# POT_10x8.net
KiCad netlist of a schematic drawn in Altium Designer
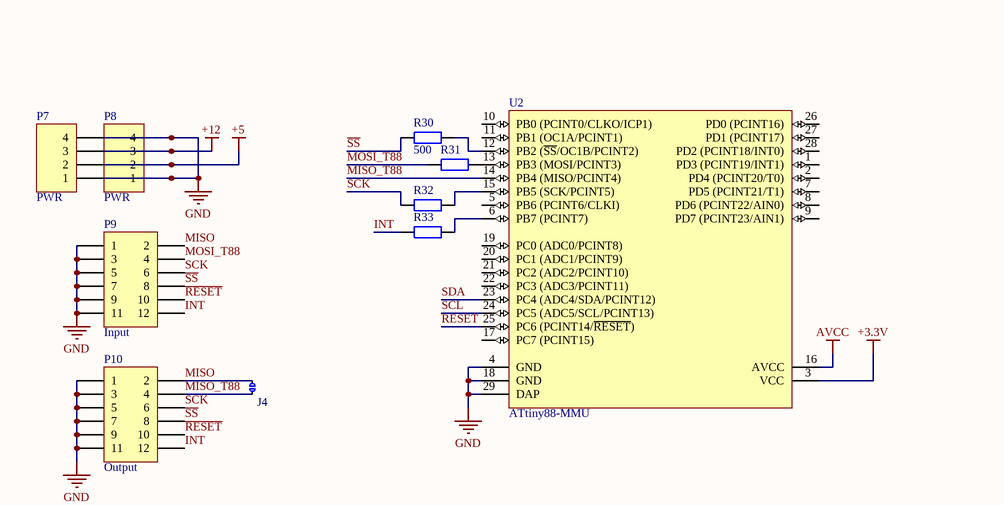
[diagram p0: POT 10x8.SchDoc, top left]
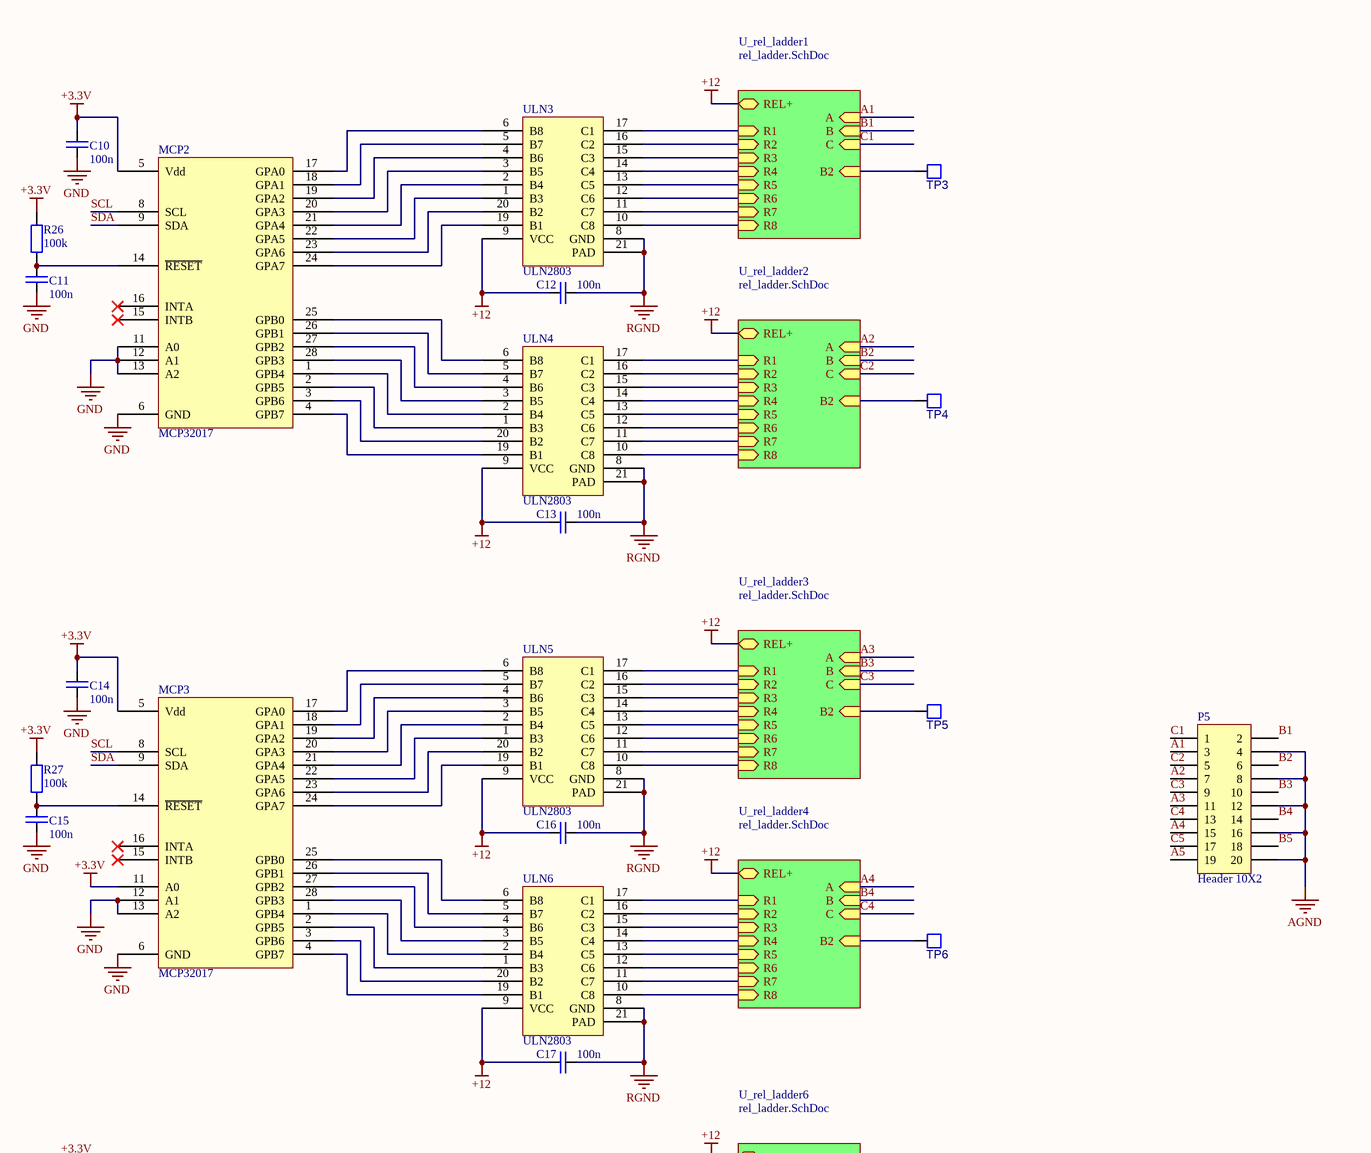
[diagram p1: POT 10x8.SchDoc, top right]
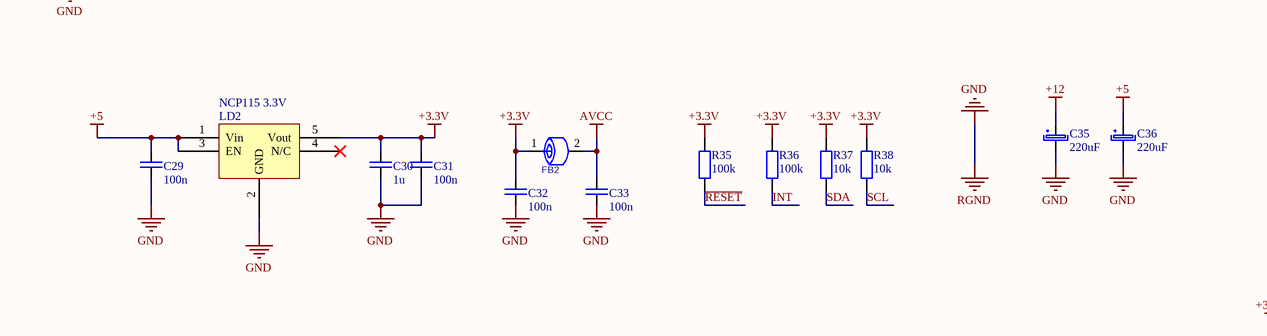
[diagram p2: POT 10x8.SchDoc, bottom left]
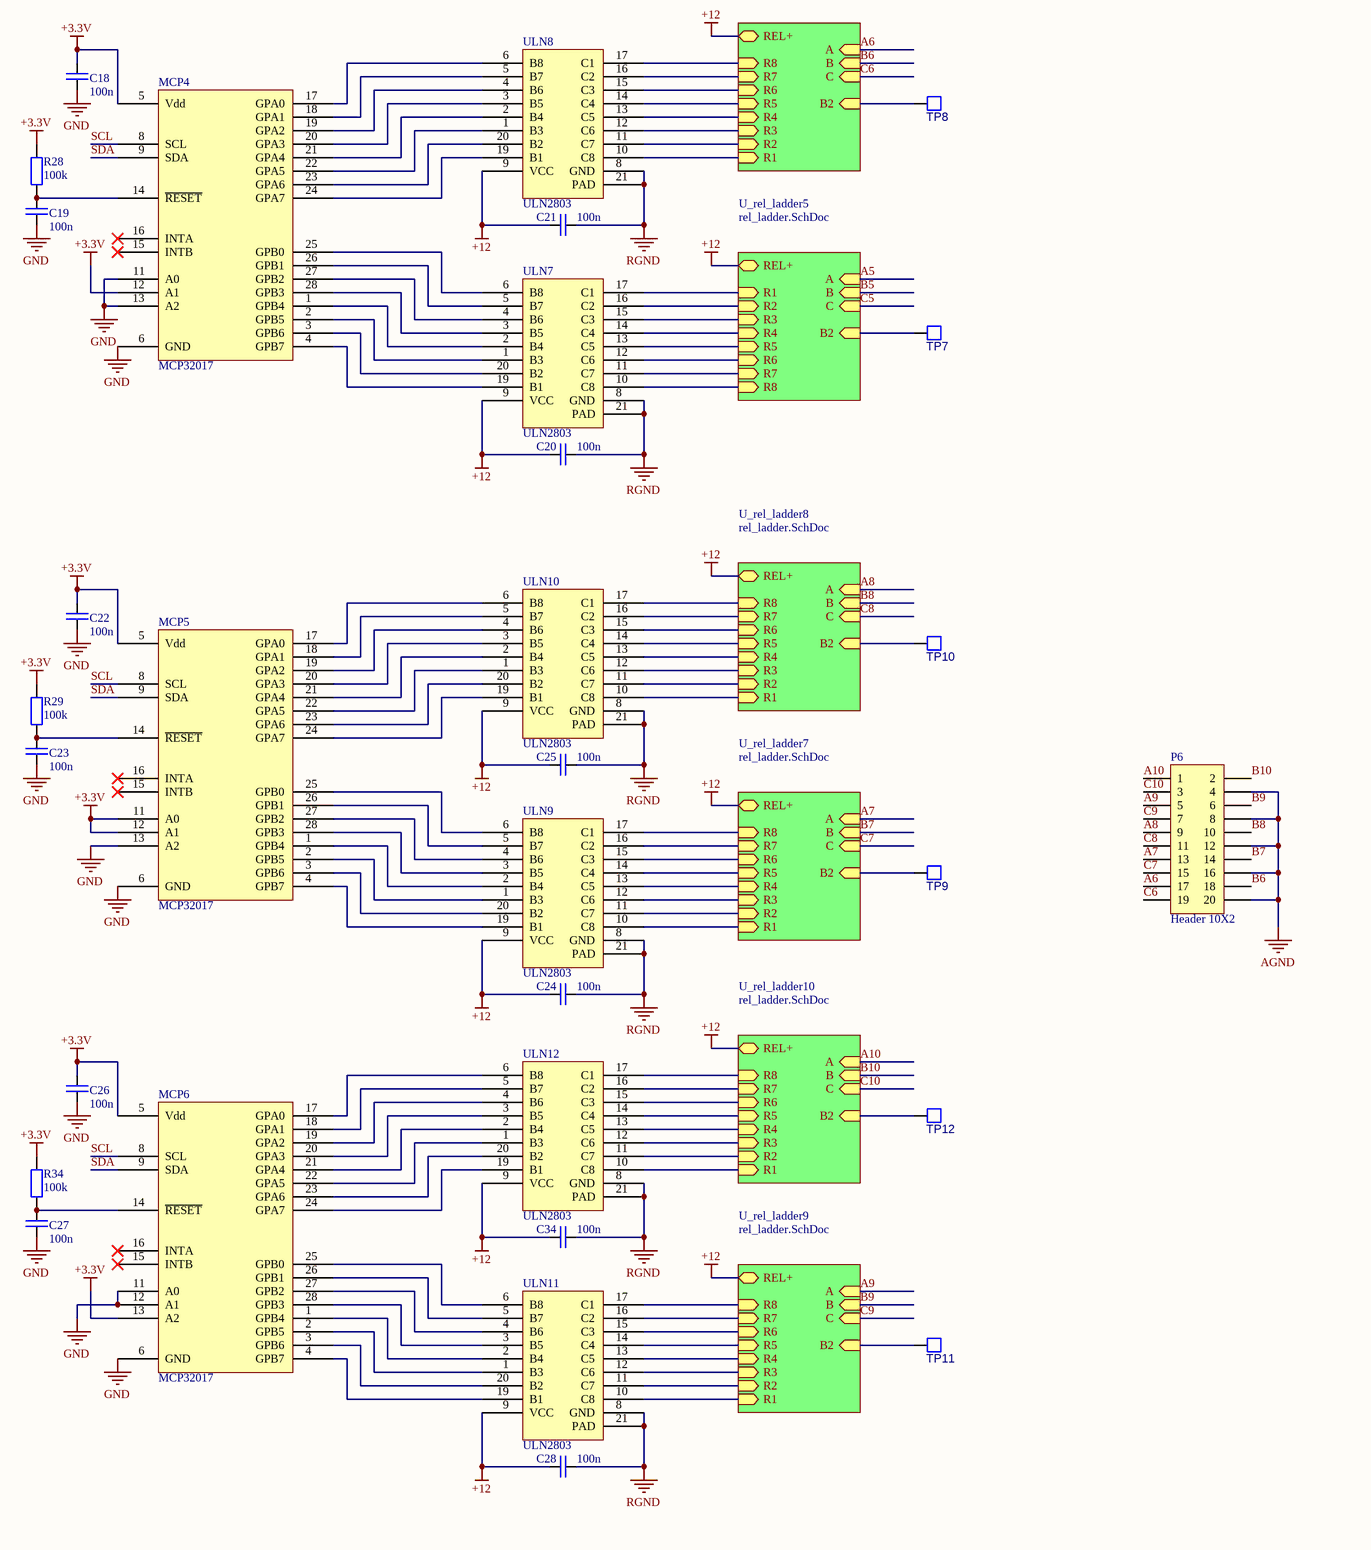
[diagram p3: POT 10x8.SchDoc, bottom right]

(export (version "E")
  (design (tool "Eeschema 10.0.6"))
  (components
    (comp (ref "C10")
      (value "100n")
      (footprint "R1005_0402i_L")
      (description "Capacitor")
      (libsource (lib "General") (part "C"))
    )
    (comp (ref "C11")
      (value "100n")
      (footprint "R1005_0402i_L")
      (description "Capacitor")
      (libsource (lib "General") (part "C"))
    )
    (comp (ref "C12")
      (value "100n")
      (footprint "R1005_0402i_L")
      (description "Capacitor")
      (libsource (lib "General") (part "C"))
    )
    (comp (ref "C13")
      (value "100n")
      (footprint "R1005_0402i_L")
      (description "Capacitor")
      (libsource (lib "General") (part "C"))
    )
    (comp (ref "C14")
      (value "100n")
      (footprint "R1005_0402i_L")
      (description "Capacitor")
      (libsource (lib "General") (part "C"))
    )
    (comp (ref "C15")
      (value "100n")
      (footprint "R1005_0402i_L")
      (description "Capacitor")
      (libsource (lib "General") (part "C"))
    )
    (comp (ref "C16")
      (value "100n")
      (footprint "R1005_0402i_L")
      (description "Capacitor")
      (libsource (lib "General") (part "C"))
    )
    (comp (ref "C17")
      (value "100n")
      (footprint "R1005_0402i_L")
      (description "Capacitor")
      (libsource (lib "General") (part "C"))
    )
    (comp (ref "C18")
      (value "100n")
      (footprint "R1005_0402i_L")
      (description "Capacitor")
      (libsource (lib "General") (part "C"))
    )
    (comp (ref "C19")
      (value "100n")
      (footprint "R1005_0402i_L")
      (description "Capacitor")
      (libsource (lib "General") (part "C"))
    )
    (comp (ref "C20")
      (value "100n")
      (footprint "R1005_0402i_L")
      (description "Capacitor")
      (libsource (lib "General") (part "C"))
    )
    (comp (ref "C21")
      (value "100n")
      (footprint "R1005_0402i_L")
      (description "Capacitor")
      (libsource (lib "General") (part "C"))
    )
    (comp (ref "C22")
      (value "100n")
      (footprint "R1005_0402i_L")
      (description "Capacitor")
      (libsource (lib "General") (part "C"))
    )
    (comp (ref "C23")
      (value "100n")
      (footprint "R1005_0402i_L")
      (description "Capacitor")
      (libsource (lib "General") (part "C"))
    )
    (comp (ref "C24")
      (value "100n")
      (footprint "R1005_0402i_L")
      (description "Capacitor")
      (libsource (lib "General") (part "C"))
    )
    (comp (ref "C25")
      (value "100n")
      (footprint "R1005_0402i_L")
      (description "Capacitor")
      (libsource (lib "General") (part "C"))
    )
    (comp (ref "C26")
      (value "100n")
      (footprint "R1005_0402i_L")
      (description "Capacitor")
      (libsource (lib "General") (part "C"))
    )
    (comp (ref "C27")
      (value "100n")
      (footprint "R1005_0402i_L")
      (description "Capacitor")
      (libsource (lib "General") (part "C"))
    )
    (comp (ref "C28")
      (value "100n")
      (footprint "R1005_0402i_L")
      (description "Capacitor")
      (libsource (lib "General") (part "C"))
    )
    (comp (ref "C29")
      (value "100n")
      (footprint "R1005_0402i_L")
      (description "Capacitor")
      (libsource (lib "General") (part "C"))
    )
    (comp (ref "C30")
      (value "1u")
      (footprint "C1608_0603I_L")
      (description "Capacitor")
      (libsource (lib "General") (part "C"))
    )
    (comp (ref "C31")
      (value "100n")
      (footprint "R1005_0402i_L")
      (description "Capacitor")
      (libsource (lib "General") (part "C"))
    )
    (comp (ref "C32")
      (value "100n")
      (footprint "R1005_0402i_L")
      (description "Capacitor")
      (libsource (lib "General") (part "C"))
    )
    (comp (ref "C33")
      (value "100n")
      (footprint "R1005_0402i_L")
      (description "Capacitor")
      (libsource (lib "General") (part "C"))
    )
    (comp (ref "C34")
      (value "100n")
      (footprint "R1005_0402i_L")
      (description "Capacitor")
      (libsource (lib "General") (part "C"))
    )
    (comp (ref "C35")
      (value "220uF")
      (footprint "C AlElko 5x11 R2")
      (description "Capacitor Polarized")
      (libsource (lib "General") (part "C+"))
    )
    (comp (ref "C36")
      (value "220uF")
      (footprint "C AlElko 5x11 R2")
      (description "Capacitor Polarized")
      (libsource (lib "General") (part "C+"))
    )
    (comp (ref "FB2")
      (value "FERITTE BEAD")
      (footprint "R1608_0603I_L")
      (libsource (lib "General") (part "FERITTE BEAD"))
    )
    (comp (ref "J4")
      (value "Terminator")
      (footprint "solderJumper")
      (libsource (lib "Kon_Tipk") (part "JMP_mini"))
    )
    (comp (ref "LD2")
      (value "NCP115 3.3V")
      (footprint "TSOP95P280X110-6L")
      (libsource (lib "led_ring") (part "NCP115 3.3V"))
    )
    (comp (ref "MCP2")
      (value "MCP32017")
      (footprint "MCP23017 QFN")
      (libsource (lib "Schlib1") (part "MCP32017"))
    )
    (comp (ref "MCP3")
      (value "MCP32017")
      (footprint "MCP23017 QFN")
      (libsource (lib "Schlib1") (part "MCP32017"))
    )
    (comp (ref "MCP4")
      (value "MCP32017")
      (footprint "MCP23017 QFN")
      (libsource (lib "Schlib1") (part "MCP32017"))
    )
    (comp (ref "MCP5")
      (value "MCP32017")
      (footprint "MCP23017 QFN")
      (libsource (lib "Schlib1") (part "MCP32017"))
    )
    (comp (ref "MCP6")
      (value "MCP32017")
      (footprint "MCP23017 QFN")
      (libsource (lib "Schlib1") (part "MCP32017"))
    )
    (comp (ref "P5")
      (value "Header 10X2")
      (footprint "HDR2X10")
      (description "Header, 10-Pin, Dual row")
      (fields (field (name "PUBLISHER") "Altium Limited"))
      (libsource (lib "Miscellaneous Connectors") (part "Header 10X2"))
    )
    (comp (ref "P6")
      (value "Header 10X2")
      (footprint "HDR2X10")
      (description "Header, 10-Pin, Dual row")
      (fields (field (name "PUBLISHER") "Altium Limited"))
      (libsource (lib "Miscellaneous Connectors") (part "Header 10X2"))
    )
    (comp (ref "P7")
      (value "PWR")
      (footprint "HDR1X4")
      (description "Header, 4-Pin")
      (fields (field (name "PUBLISHER") "Altium Limited"))
      (libsource (lib "Miscellaneous Connectors") (part "Header 4"))
    )
    (comp (ref "P8")
      (value "PWR")
      (footprint "HDR1X4")
      (description "Header, 4-Pin")
      (fields (field (name "PUBLISHER") "Altium Limited"))
      (libsource (lib "Miscellaneous Connectors") (part "Header 4"))
    )
    (comp (ref "P9")
      (value "Input")
      (footprint "1.27mm SMD conn")
      (description "Header, 6-Pin, Dual row")
      (fields (field (name "PUBLISHER") "Altium Limited"))
      (libsource (lib "Miscellaneous Connectors") (part "Header 6X2"))
    )
    (comp (ref "P10")
      (value "Output")
      (footprint "1.27mm SMD conn")
      (description "Header, 6-Pin, Dual row")
      (fields (field (name "PUBLISHER") "Altium Limited"))
      (libsource (lib "Miscellaneous Connectors") (part "Header 6X2"))
    )
    (comp (ref "R26")
      (value "100k")
      (footprint "R1005_0402i_L")
      (description "R")
      (libsource (lib "General") (part "R"))
    )
    (comp (ref "R27")
      (value "100k")
      (footprint "R1005_0402i_L")
      (description "R")
      (libsource (lib "General") (part "R"))
    )
    (comp (ref "R28")
      (value "100k")
      (footprint "R1005_0402i_L")
      (description "R")
      (libsource (lib "General") (part "R"))
    )
    (comp (ref "R29")
      (value "100k")
      (footprint "R1005_0402i_L")
      (description "R")
      (libsource (lib "General") (part "R"))
    )
    (comp (ref "R30")
      (value "500")
      (footprint "R1005_0402i_L")
      (description "R")
      (libsource (lib "General") (part "R"))
    )
    (comp (ref "R31")
      (value "500")
      (footprint "R1005_0402i_L")
      (description "R")
      (libsource (lib "General") (part "R"))
    )
    (comp (ref "R32")
      (value "500")
      (footprint "R1005_0402i_L")
      (description "R")
      (libsource (lib "General") (part "R"))
    )
    (comp (ref "R33")
      (value "500")
      (footprint "R1005_0402i_L")
      (description "R")
      (libsource (lib "General") (part "R"))
    )
    (comp (ref "R34")
      (value "100k")
      (footprint "R1005_0402i_L")
      (description "R")
      (libsource (lib "General") (part "R"))
    )
    (comp (ref "R35")
      (value "100k")
      (footprint "R1005_0402i_L")
      (description "R")
      (libsource (lib "General") (part "R"))
    )
    (comp (ref "R36")
      (value "100k")
      (footprint "R1005_0402i_L")
      (description "R")
      (libsource (lib "General") (part "R"))
    )
    (comp (ref "R37")
      (value "10k")
      (footprint "R1005_0402i_L")
      (description "R")
      (libsource (lib "General") (part "R"))
    )
    (comp (ref "R38")
      (value "10k")
      (footprint "R1005_0402i_L")
      (description "R")
      (libsource (lib "General") (part "R"))
    )
    (comp (ref "TP3") (value "PAD") (footprint "PAD_CIRC_HOLE") (libsource (lib "General") (part "PAD")))
    (comp (ref "TP4") (value "PAD") (footprint "PAD_CIRC_HOLE") (libsource (lib "General") (part "PAD")))
    (comp (ref "TP5") (value "PAD") (footprint "PAD_CIRC_HOLE") (libsource (lib "General") (part "PAD")))
    (comp (ref "TP6") (value "PAD") (footprint "PAD_CIRC_HOLE") (libsource (lib "General") (part "PAD")))
    (comp (ref "TP7") (value "PAD") (footprint "PAD_CIRC_HOLE") (libsource (lib "General") (part "PAD")))
    (comp (ref "TP8") (value "PAD") (footprint "PAD_CIRC_HOLE") (libsource (lib "General") (part "PAD")))
    (comp (ref "TP9") (value "PAD") (footprint "PAD_CIRC_HOLE") (libsource (lib "General") (part "PAD")))
    (comp (ref "TP10") (value "PAD") (footprint "PAD_CIRC_HOLE") (libsource (lib "General") (part "PAD")))
    (comp (ref "TP11") (value "PAD") (footprint "PAD_CIRC_HOLE") (libsource (lib "General") (part "PAD")))
    (comp (ref "TP12") (value "PAD") (footprint "PAD_CIRC_HOLE") (libsource (lib "General") (part "PAD")))
    (comp (ref "U2")
      (value "ATtiny88-MMU")
      (footprint "28M1_N")
      (fields (field (name "PUBLISHER") "Altium Limited"))
      (libsource (lib "Encoder_w_LED_ring") (part "ATtiny88-MMU"))
    )
    (comp (ref "ULN3")
      (value "ULN2803")
      (footprint "QFN127P600-8N")
      (libsource (lib "Schlib1") (part "ULN2803"))
    )
    (comp (ref "ULN4")
      (value "ULN2803")
      (footprint "QFN127P600-8N")
      (libsource (lib "Schlib1") (part "ULN2803"))
    )
    (comp (ref "ULN5")
      (value "ULN2803")
      (footprint "QFN127P600-8N")
      (libsource (lib "Schlib1") (part "ULN2803"))
    )
    (comp (ref "ULN6")
      (value "ULN2803")
      (footprint "QFN127P600-8N")
      (libsource (lib "Schlib1") (part "ULN2803"))
    )
    (comp (ref "ULN7")
      (value "ULN2803")
      (footprint "QFN127P600-8N")
      (libsource (lib "Schlib1") (part "ULN2803"))
    )
    (comp (ref "ULN8")
      (value "ULN2803")
      (footprint "QFN127P600-8N")
      (libsource (lib "Schlib1") (part "ULN2803"))
    )
    (comp (ref "ULN9")
      (value "ULN2803")
      (footprint "QFN127P600-8N")
      (libsource (lib "Schlib1") (part "ULN2803"))
    )
    (comp (ref "ULN10")
      (value "ULN2803")
      (footprint "QFN127P600-8N")
      (libsource (lib "Schlib1") (part "ULN2803"))
    )
    (comp (ref "ULN11")
      (value "ULN2803")
      (footprint "QFN127P600-8N")
      (libsource (lib "Schlib1") (part "ULN2803"))
    )
    (comp (ref "ULN12")
      (value "ULN2803")
      (footprint "QFN127P600-8N")
      (libsource (lib "Schlib1") (part "ULN2803"))
    )
  )
  (nets
    (net (code "1") (name "+3.3V") (class "Default")
      (node (ref "C10") (pin "2") (pinfunction "2_2") (pintype "passive"))
      (node (ref "C14") (pin "2") (pinfunction "2_2") (pintype "passive"))
      (node (ref "C18") (pin "2") (pinfunction "2_2") (pintype "passive"))
      (node (ref "C22") (pin "2") (pinfunction "2_2") (pintype "passive"))
      (node (ref "C26") (pin "2") (pinfunction "2_2") (pintype "passive"))
      (node (ref "C30") (pin "1") (pinfunction "1_1") (pintype "passive"))
      (node (ref "C31") (pin "1") (pinfunction "1_1") (pintype "passive"))
      (node (ref "C32") (pin "1") (pinfunction "1_1") (pintype "passive"))
      (node (ref "FB2") (pin "1") (pintype "passive"))
      (node (ref "LD2") (pin "5") (pinfunction "Vout_5") (pintype "passive"))
      (node (ref "MCP2") (pin "5") (pinfunction "Vdd_5") (pintype "passive"))
      (node (ref "MCP3") (pin "11") (pinfunction "A0_11") (pintype "passive"))
      (node (ref "MCP3") (pin "5") (pinfunction "Vdd_5") (pintype "passive"))
      (node (ref "MCP4") (pin "12") (pinfunction "A1_12") (pintype "passive"))
      (node (ref "MCP4") (pin "5") (pinfunction "Vdd_5") (pintype "passive"))
      (node (ref "MCP5") (pin "11") (pinfunction "A0_11") (pintype "passive"))
      (node (ref "MCP5") (pin "12") (pinfunction "A1_12") (pintype "passive"))
      (node (ref "MCP5") (pin "5") (pinfunction "Vdd_5") (pintype "passive"))
      (node (ref "MCP6") (pin "13") (pinfunction "A2_13") (pintype "passive"))
      (node (ref "MCP6") (pin "5") (pinfunction "Vdd_5") (pintype "passive"))
      (node (ref "R26") (pin "1") (pintype "passive"))
      (node (ref "R27") (pin "1") (pintype "passive"))
      (node (ref "R28") (pin "1") (pintype "passive"))
      (node (ref "R29") (pin "1") (pintype "passive"))
      (node (ref "R34") (pin "1") (pintype "passive"))
      (node (ref "R35") (pin "1") (pintype "passive"))
      (node (ref "R36") (pin "1") (pintype "passive"))
      (node (ref "R37") (pin "1") (pintype "passive"))
      (node (ref "R38") (pin "1") (pintype "passive"))
      (node (ref "U2") (pin "3") (pinfunction "VCC_3") (pintype "power_in"))
    )
    (net (code "2") (name "+5") (class "Default")
      (node (ref "C29") (pin "1") (pinfunction "1_1") (pintype "passive"))
      (node (ref "C36") (pin "1") (pinfunction "1_1") (pintype "passive"))
      (node (ref "LD2") (pin "1") (pinfunction "Vin_1") (pintype "passive"))
      (node (ref "LD2") (pin "3") (pinfunction "EN_3") (pintype "passive"))
      (node (ref "P7") (pin "2") (pinfunction "2_2") (pintype "passive"))
      (node (ref "P8") (pin "2") (pinfunction "2_2") (pintype "passive"))
    )
    (net (code "3") (name "+12") (class "Default")
      (node (ref "C12") (pin "1") (pinfunction "1_1") (pintype "passive"))
      (node (ref "C13") (pin "1") (pinfunction "1_1") (pintype "passive"))
      (node (ref "C16") (pin "1") (pinfunction "1_1") (pintype "passive"))
      (node (ref "C17") (pin "1") (pinfunction "1_1") (pintype "passive"))
      (node (ref "C20") (pin "1") (pinfunction "1_1") (pintype "passive"))
      (node (ref "C21") (pin "1") (pinfunction "1_1") (pintype "passive"))
      (node (ref "C24") (pin "1") (pinfunction "1_1") (pintype "passive"))
      (node (ref "C25") (pin "1") (pinfunction "1_1") (pintype "passive"))
      (node (ref "C28") (pin "1") (pinfunction "1_1") (pintype "passive"))
      (node (ref "C34") (pin "1") (pinfunction "1_1") (pintype "passive"))
      (node (ref "C35") (pin "1") (pinfunction "1_1") (pintype "passive"))
      (node (ref "P7") (pin "3") (pinfunction "3_3") (pintype "passive"))
      (node (ref "P8") (pin "3") (pinfunction "3_3") (pintype "passive"))
      (node (ref "ULN10") (pin "9") (pinfunction "VCC_9") (pintype "passive"))
      (node (ref "ULN11") (pin "9") (pinfunction "VCC_9") (pintype "passive"))
      (node (ref "ULN12") (pin "9") (pinfunction "VCC_9") (pintype "passive"))
      (node (ref "ULN3") (pin "9") (pinfunction "VCC_9") (pintype "passive"))
      (node (ref "ULN4") (pin "9") (pinfunction "VCC_9") (pintype "passive"))
      (node (ref "ULN5") (pin "9") (pinfunction "VCC_9") (pintype "passive"))
      (node (ref "ULN6") (pin "9") (pinfunction "VCC_9") (pintype "passive"))
      (node (ref "ULN7") (pin "9") (pinfunction "VCC_9") (pintype "passive"))
      (node (ref "ULN8") (pin "9") (pinfunction "VCC_9") (pintype "passive"))
      (node (ref "ULN9") (pin "9") (pinfunction "VCC_9") (pintype "passive"))
    )
    (net (code "4") (name "/A1") (class "Default")
      (node (ref "P5") (pin "3") (pinfunction "3_3") (pintype "passive"))
    )
    (net (code "5") (name "/A2") (class "Default")
      (node (ref "P5") (pin "7") (pinfunction "7_7") (pintype "passive"))
    )
    (net (code "6") (name "/A3") (class "Default")
      (node (ref "P5") (pin "11") (pinfunction "11_11") (pintype "passive"))
    )
    (net (code "7") (name "/A4") (class "Default")
      (node (ref "P5") (pin "15") (pinfunction "15_15") (pintype "passive"))
    )
    (net (code "8") (name "/A5") (class "Default")
      (node (ref "P5") (pin "19") (pinfunction "19_19") (pintype "passive"))
    )
    (net (code "9") (name "/A6") (class "Default")
      (node (ref "P6") (pin "17") (pinfunction "17_17") (pintype "passive"))
    )
    (net (code "10") (name "/A7") (class "Default")
      (node (ref "P6") (pin "13") (pinfunction "13_13") (pintype "passive"))
    )
    (net (code "11") (name "/A8") (class "Default")
      (node (ref "P6") (pin "9") (pinfunction "9_9") (pintype "passive"))
    )
    (net (code "12") (name "/A9") (class "Default")
      (node (ref "P6") (pin "5") (pinfunction "5_5") (pintype "passive"))
    )
    (net (code "13") (name "/A10") (class "Default")
      (node (ref "P6") (pin "1") (pinfunction "1_1") (pintype "passive"))
    )
    (net (code "14") (name "/B1") (class "Default")
      (node (ref "P5") (pin "2") (pinfunction "2_2") (pintype "passive"))
    )
    (net (code "15") (name "/B2") (class "Default")
      (node (ref "P5") (pin "6") (pinfunction "6_6") (pintype "passive"))
    )
    (net (code "16") (name "/B2_1") (class "Default")
      (node (ref "TP3") (pin "1") (pinfunction "1_1") (pintype "passive"))
    )
    (net (code "17") (name "/B2_2") (class "Default")
      (node (ref "TP5") (pin "1") (pinfunction "1_1") (pintype "passive"))
    )
    (net (code "18") (name "/B2_3") (class "Default")
      (node (ref "TP4") (pin "1") (pinfunction "1_1") (pintype "passive"))
    )
    (net (code "19") (name "/B2_4") (class "Default")
      (node (ref "TP11") (pin "1") (pinfunction "1_1") (pintype "passive"))
    )
    (net (code "20") (name "/B2_5") (class "Default")
      (node (ref "TP12") (pin "1") (pinfunction "1_1") (pintype "passive"))
    )
    (net (code "21") (name "/B2_6") (class "Default")
      (node (ref "TP9") (pin "1") (pinfunction "1_1") (pintype "passive"))
    )
    (net (code "22") (name "/B2_7") (class "Default")
      (node (ref "TP7") (pin "1") (pinfunction "1_1") (pintype "passive"))
    )
    (net (code "23") (name "/B2_8") (class "Default")
      (node (ref "TP8") (pin "1") (pinfunction "1_1") (pintype "passive"))
    )
    (net (code "24") (name "/B2_9") (class "Default")
      (node (ref "TP6") (pin "1") (pinfunction "1_1") (pintype "passive"))
    )
    (net (code "25") (name "/B2_10") (class "Default")
      (node (ref "TP10") (pin "1") (pinfunction "1_1") (pintype "passive"))
    )
    (net (code "26") (name "/B3") (class "Default")
      (node (ref "P5") (pin "10") (pinfunction "10_10") (pintype "passive"))
    )
    (net (code "27") (name "/B4") (class "Default")
      (node (ref "P5") (pin "14") (pinfunction "14_14") (pintype "passive"))
    )
    (net (code "28") (name "/B5") (class "Default")
      (node (ref "P5") (pin "18") (pinfunction "18_18") (pintype "passive"))
    )
    (net (code "29") (name "/B6") (class "Default")
      (node (ref "P6") (pin "18") (pinfunction "18_18") (pintype "passive"))
    )
    (net (code "30") (name "/B7") (class "Default")
      (node (ref "P6") (pin "14") (pinfunction "14_14") (pintype "passive"))
    )
    (net (code "31") (name "/B8") (class "Default")
      (node (ref "P6") (pin "10") (pinfunction "10_10") (pintype "passive"))
    )
    (net (code "32") (name "/B9") (class "Default")
      (node (ref "P6") (pin "6") (pinfunction "6_6") (pintype "passive"))
    )
    (net (code "33") (name "/B10") (class "Default")
      (node (ref "P6") (pin "2") (pinfunction "2_2") (pintype "passive"))
    )
    (net (code "34") (name "/C1") (class "Default")
      (node (ref "P5") (pin "1") (pinfunction "1_1") (pintype "passive"))
    )
    (net (code "35") (name "/C2") (class "Default")
      (node (ref "P5") (pin "5") (pinfunction "5_5") (pintype "passive"))
    )
    (net (code "36") (name "/C3") (class "Default")
      (node (ref "P5") (pin "9") (pinfunction "9_9") (pintype "passive"))
    )
    (net (code "37") (name "/C4") (class "Default")
      (node (ref "P5") (pin "13") (pinfunction "13_13") (pintype "passive"))
    )
    (net (code "38") (name "/C5") (class "Default")
      (node (ref "P5") (pin "17") (pinfunction "17_17") (pintype "passive"))
    )
    (net (code "39") (name "/C6") (class "Default")
      (node (ref "P6") (pin "19") (pinfunction "19_19") (pintype "passive"))
    )
    (net (code "40") (name "/C7") (class "Default")
      (node (ref "P6") (pin "15") (pinfunction "15_15") (pintype "passive"))
    )
    (net (code "41") (name "/C8") (class "Default")
      (node (ref "P6") (pin "11") (pinfunction "11_11") (pintype "passive"))
    )
    (net (code "42") (name "/C9") (class "Default")
      (node (ref "P6") (pin "7") (pinfunction "7_7") (pintype "passive"))
    )
    (net (code "43") (name "/C10") (class "Default")
      (node (ref "P6") (pin "3") (pinfunction "3_3") (pintype "passive"))
    )
    (net (code "44") (name "/INT") (class "Default")
      (node (ref "P10") (pin "12") (pinfunction "12_12") (pintype "passive"))
      (node (ref "P9") (pin "12") (pinfunction "12_12") (pintype "passive"))
      (node (ref "R33") (pin "1") (pintype "passive"))
      (node (ref "R36") (pin "2") (pintype "passive"))
    )
    (net (code "45") (name "/MISO") (class "Default")
      (node (ref "J4") (pin "2") (pinfunction "2_2") (pintype "passive"))
      (node (ref "P10") (pin "2") (pinfunction "2_2") (pintype "passive"))
      (node (ref "P9") (pin "2") (pinfunction "2_2") (pintype "passive"))
    )
    (net (code "46") (name "/MISO_T88") (class "Default")
      (node (ref "J4") (pin "1") (pinfunction "1_1") (pintype "passive"))
      (node (ref "P10") (pin "4") (pinfunction "4_4") (pintype "passive"))
      (node (ref "U2") (pin "14") (pinfunction "PB4_(MISO/PCINT4)_14") (pintype "bidirectional"))
    )
    (net (code "47") (name "/MOSI_T88") (class "Default")
      (node (ref "P9") (pin "4") (pinfunction "4_4") (pintype "passive"))
      (node (ref "R31") (pin "1") (pintype "passive"))
    )
    (net (code "48") (name "/R1") (class "Default")
      (node (ref "ULN6") (pin "17") (pinfunction "C1_17") (pintype "passive"))
    )
    (net (code "49") (name "/R1_1") (class "Default")
      (node (ref "ULN4") (pin "17") (pinfunction "C1_17") (pintype "passive"))
    )
    (net (code "50") (name "/R1_2") (class "Default")
      (node (ref "ULN5") (pin "17") (pinfunction "C1_17") (pintype "passive"))
    )
    (net (code "51") (name "/R1_3") (class "Default")
      (node (ref "ULN3") (pin "17") (pinfunction "C1_17") (pintype "passive"))
    )
    (net (code "52") (name "/R1_4") (class "Default")
      (node (ref "ULN11") (pin "10") (pinfunction "C8_10") (pintype "passive"))
    )
    (net (code "53") (name "/R1_5") (class "Default")
      (node (ref "ULN9") (pin "10") (pinfunction "C8_10") (pintype "passive"))
    )
    (net (code "54") (name "/R1_6") (class "Default")
      (node (ref "ULN12") (pin "10") (pinfunction "C8_10") (pintype "passive"))
    )
    (net (code "55") (name "/R1_7") (class "Default")
      (node (ref "ULN8") (pin "10") (pinfunction "C8_10") (pintype "passive"))
    )
    (net (code "56") (name "/R1_8") (class "Default")
      (node (ref "ULN7") (pin "17") (pinfunction "C1_17") (pintype "passive"))
    )
    (net (code "57") (name "/R1_9") (class "Default")
      (node (ref "ULN10") (pin "10") (pinfunction "C8_10") (pintype "passive"))
    )
    (net (code "58") (name "/R2") (class "Default")
      (node (ref "ULN6") (pin "16") (pinfunction "C2_16") (pintype "passive"))
    )
    (net (code "59") (name "/R2_1") (class "Default")
      (node (ref "ULN4") (pin "16") (pinfunction "C2_16") (pintype "passive"))
    )
    (net (code "60") (name "/R2_2") (class "Default")
      (node (ref "ULN5") (pin "16") (pinfunction "C2_16") (pintype "passive"))
    )
    (net (code "61") (name "/R2_3") (class "Default")
      (node (ref "ULN3") (pin "16") (pinfunction "C2_16") (pintype "passive"))
    )
    (net (code "62") (name "/R2_4") (class "Default")
      (node (ref "ULN11") (pin "11") (pinfunction "C7_11") (pintype "passive"))
    )
    (net (code "63") (name "/R2_5") (class "Default")
      (node (ref "ULN9") (pin "11") (pinfunction "C7_11") (pintype "passive"))
    )
    (net (code "64") (name "/R2_6") (class "Default")
      (node (ref "ULN12") (pin "11") (pinfunction "C7_11") (pintype "passive"))
    )
    (net (code "65") (name "/R2_7") (class "Default")
      (node (ref "ULN8") (pin "11") (pinfunction "C7_11") (pintype "passive"))
    )
    (net (code "66") (name "/R2_8") (class "Default")
      (node (ref "ULN7") (pin "16") (pinfunction "C2_16") (pintype "passive"))
    )
    (net (code "67") (name "/R2_9") (class "Default")
      (node (ref "ULN10") (pin "11") (pinfunction "C7_11") (pintype "passive"))
    )
    (net (code "68") (name "/R3") (class "Default")
      (node (ref "ULN6") (pin "15") (pinfunction "C3_15") (pintype "passive"))
    )
    (net (code "69") (name "/R3_1") (class "Default")
      (node (ref "ULN4") (pin "15") (pinfunction "C3_15") (pintype "passive"))
    )
    (net (code "70") (name "/R3_2") (class "Default")
      (node (ref "ULN5") (pin "15") (pinfunction "C3_15") (pintype "passive"))
    )
    (net (code "71") (name "/R3_3") (class "Default")
      (node (ref "ULN3") (pin "15") (pinfunction "C3_15") (pintype "passive"))
    )
    (net (code "72") (name "/R3_4") (class "Default")
      (node (ref "ULN11") (pin "12") (pinfunction "C6_12") (pintype "passive"))
    )
    (net (code "73") (name "/R3_5") (class "Default")
      (node (ref "ULN9") (pin "12") (pinfunction "C6_12") (pintype "passive"))
    )
    (net (code "74") (name "/R3_6") (class "Default")
      (node (ref "ULN12") (pin "12") (pinfunction "C6_12") (pintype "passive"))
    )
    (net (code "75") (name "/R3_7") (class "Default")
      (node (ref "ULN8") (pin "12") (pinfunction "C6_12") (pintype "passive"))
    )
    (net (code "76") (name "/R3_8") (class "Default")
      (node (ref "ULN7") (pin "15") (pinfunction "C3_15") (pintype "passive"))
    )
    (net (code "77") (name "/R3_9") (class "Default")
      (node (ref "ULN10") (pin "12") (pinfunction "C6_12") (pintype "passive"))
    )
    (net (code "78") (name "/R4") (class "Default")
      (node (ref "ULN6") (pin "14") (pinfunction "C4_14") (pintype "passive"))
    )
    (net (code "79") (name "/R4_1") (class "Default")
      (node (ref "ULN4") (pin "14") (pinfunction "C4_14") (pintype "passive"))
    )
    (net (code "80") (name "/R4_2") (class "Default")
      (node (ref "ULN5") (pin "14") (pinfunction "C4_14") (pintype "passive"))
    )
    (net (code "81") (name "/R4_3") (class "Default")
      (node (ref "ULN3") (pin "14") (pinfunction "C4_14") (pintype "passive"))
    )
    (net (code "82") (name "/R4_4") (class "Default")
      (node (ref "ULN11") (pin "13") (pinfunction "C5_13") (pintype "passive"))
    )
    (net (code "83") (name "/R4_5") (class "Default")
      (node (ref "ULN9") (pin "13") (pinfunction "C5_13") (pintype "passive"))
    )
    (net (code "84") (name "/R4_6") (class "Default")
      (node (ref "ULN12") (pin "13") (pinfunction "C5_13") (pintype "passive"))
    )
    (net (code "85") (name "/R4_7") (class "Default")
      (node (ref "ULN8") (pin "13") (pinfunction "C5_13") (pintype "passive"))
    )
    (net (code "86") (name "/R4_8") (class "Default")
      (node (ref "ULN7") (pin "14") (pinfunction "C4_14") (pintype "passive"))
    )
    (net (code "87") (name "/R4_9") (class "Default")
      (node (ref "ULN10") (pin "13") (pinfunction "C5_13") (pintype "passive"))
    )
    (net (code "88") (name "/R5") (class "Default")
      (node (ref "ULN6") (pin "13") (pinfunction "C5_13") (pintype "passive"))
    )
    (net (code "89") (name "/R5_1") (class "Default")
      (node (ref "ULN4") (pin "13") (pinfunction "C5_13") (pintype "passive"))
    )
    (net (code "90") (name "/R5_2") (class "Default")
      (node (ref "ULN5") (pin "13") (pinfunction "C5_13") (pintype "passive"))
    )
    (net (code "91") (name "/R5_3") (class "Default")
      (node (ref "ULN3") (pin "13") (pinfunction "C5_13") (pintype "passive"))
    )
    (net (code "92") (name "/R5_4") (class "Default")
      (node (ref "ULN11") (pin "14") (pinfunction "C4_14") (pintype "passive"))
    )
    (net (code "93") (name "/R5_5") (class "Default")
      (node (ref "ULN9") (pin "14") (pinfunction "C4_14") (pintype "passive"))
    )
    (net (code "94") (name "/R5_6") (class "Default")
      (node (ref "ULN12") (pin "14") (pinfunction "C4_14") (pintype "passive"))
    )
    (net (code "95") (name "/R5_7") (class "Default")
      (node (ref "ULN8") (pin "14") (pinfunction "C4_14") (pintype "passive"))
    )
    (net (code "96") (name "/R5_8") (class "Default")
      (node (ref "ULN7") (pin "13") (pinfunction "C5_13") (pintype "passive"))
    )
    (net (code "97") (name "/R5_9") (class "Default")
      (node (ref "ULN10") (pin "14") (pinfunction "C4_14") (pintype "passive"))
    )
    (net (code "98") (name "/R6") (class "Default")
      (node (ref "ULN6") (pin "12") (pinfunction "C6_12") (pintype "passive"))
    )
    (net (code "99") (name "/R6_1") (class "Default")
      (node (ref "ULN4") (pin "12") (pinfunction "C6_12") (pintype "passive"))
    )
    (net (code "100") (name "/R6_2") (class "Default")
      (node (ref "ULN5") (pin "12") (pinfunction "C6_12") (pintype "passive"))
    )
    (net (code "101") (name "/R6_3") (class "Default")
      (node (ref "ULN3") (pin "12") (pinfunction "C6_12") (pintype "passive"))
    )
    (net (code "102") (name "/R6_4") (class "Default")
      (node (ref "ULN11") (pin "15") (pinfunction "C3_15") (pintype "passive"))
    )
    (net (code "103") (name "/R6_5") (class "Default")
      (node (ref "ULN9") (pin "15") (pinfunction "C3_15") (pintype "passive"))
    )
    (net (code "104") (name "/R6_6") (class "Default")
      (node (ref "ULN12") (pin "15") (pinfunction "C3_15") (pintype "passive"))
    )
    (net (code "105") (name "/R6_7") (class "Default")
      (node (ref "ULN8") (pin "15") (pinfunction "C3_15") (pintype "passive"))
    )
    (net (code "106") (name "/R6_8") (class "Default")
      (node (ref "ULN7") (pin "12") (pinfunction "C6_12") (pintype "passive"))
    )
    (net (code "107") (name "/R6_9") (class "Default")
      (node (ref "ULN10") (pin "15") (pinfunction "C3_15") (pintype "passive"))
    )
    (net (code "108") (name "/R7") (class "Default")
      (node (ref "ULN6") (pin "11") (pinfunction "C7_11") (pintype "passive"))
    )
    (net (code "109") (name "/R7_1") (class "Default")
      (node (ref "ULN4") (pin "11") (pinfunction "C7_11") (pintype "passive"))
    )
    (net (code "110") (name "/R7_2") (class "Default")
      (node (ref "ULN5") (pin "11") (pinfunction "C7_11") (pintype "passive"))
    )
    (net (code "111") (name "/R7_3") (class "Default")
      (node (ref "ULN3") (pin "11") (pinfunction "C7_11") (pintype "passive"))
    )
    (net (code "112") (name "/R7_4") (class "Default")
      (node (ref "ULN11") (pin "16") (pinfunction "C2_16") (pintype "passive"))
    )
    (net (code "113") (name "/R7_5") (class "Default")
      (node (ref "ULN9") (pin "16") (pinfunction "C2_16") (pintype "passive"))
    )
    (net (code "114") (name "/R7_6") (class "Default")
      (node (ref "ULN12") (pin "16") (pinfunction "C2_16") (pintype "passive"))
    )
    (net (code "115") (name "/R7_7") (class "Default")
      (node (ref "ULN8") (pin "16") (pinfunction "C2_16") (pintype "passive"))
    )
    (net (code "116") (name "/R7_8") (class "Default")
      (node (ref "ULN7") (pin "11") (pinfunction "C7_11") (pintype "passive"))
    )
    (net (code "117") (name "/R7_9") (class "Default")
      (node (ref "ULN10") (pin "16") (pinfunction "C2_16") (pintype "passive"))
    )
    (net (code "118") (name "/R8") (class "Default")
      (node (ref "ULN6") (pin "10") (pinfunction "C8_10") (pintype "passive"))
    )
    (net (code "119") (name "/R8_1") (class "Default")
      (node (ref "ULN4") (pin "10") (pinfunction "C8_10") (pintype "passive"))
    )
    (net (code "120") (name "/R8_2") (class "Default")
      (node (ref "ULN5") (pin "10") (pinfunction "C8_10") (pintype "passive"))
    )
    (net (code "121") (name "/R8_3") (class "Default")
      (node (ref "ULN3") (pin "10") (pinfunction "C8_10") (pintype "passive"))
    )
    (net (code "122") (name "/R8_4") (class "Default")
      (node (ref "ULN11") (pin "17") (pinfunction "C1_17") (pintype "passive"))
    )
    (net (code "123") (name "/R8_5") (class "Default")
      (node (ref "ULN9") (pin "17") (pinfunction "C1_17") (pintype "passive"))
    )
    (net (code "124") (name "/R8_6") (class "Default")
      (node (ref "ULN12") (pin "17") (pinfunction "C1_17") (pintype "passive"))
    )
    (net (code "125") (name "/R8_7") (class "Default")
      (node (ref "ULN8") (pin "17") (pinfunction "C1_17") (pintype "passive"))
    )
    (net (code "126") (name "/R8_8") (class "Default")
      (node (ref "ULN7") (pin "10") (pinfunction "C8_10") (pintype "passive"))
    )
    (net (code "127") (name "/R8_9") (class "Default")
      (node (ref "ULN10") (pin "17") (pinfunction "C1_17") (pintype "passive"))
    )
    (net (code "128") (name "/SCK") (class "Default")
      (node (ref "P10") (pin "6") (pinfunction "6_6") (pintype "passive"))
      (node (ref "P9") (pin "6") (pinfunction "6_6") (pintype "passive"))
      (node (ref "R32") (pin "1") (pintype "passive"))
    )
    (net (code "129") (name "/SCL") (class "Default")
      (node (ref "MCP2") (pin "8") (pinfunction "SCL_8") (pintype "passive"))
      (node (ref "MCP3") (pin "8") (pinfunction "SCL_8") (pintype "passive"))
      (node (ref "MCP4") (pin "8") (pinfunction "SCL_8") (pintype "passive"))
      (node (ref "MCP5") (pin "8") (pinfunction "SCL_8") (pintype "passive"))
      (node (ref "MCP6") (pin "8") (pinfunction "SCL_8") (pintype "passive"))
      (node (ref "R38") (pin "2") (pintype "passive"))
      (node (ref "U2") (pin "24") (pinfunction "PC5_(ADC5/SCL/PCINT13)_24") (pintype "bidirectional"))
    )
    (net (code "130") (name "/SDA") (class "Default")
      (node (ref "MCP2") (pin "9") (pinfunction "SDA_9") (pintype "passive"))
      (node (ref "MCP3") (pin "9") (pinfunction "SDA_9") (pintype "passive"))
      (node (ref "MCP4") (pin "9") (pinfunction "SDA_9") (pintype "passive"))
      (node (ref "MCP5") (pin "9") (pinfunction "SDA_9") (pintype "passive"))
      (node (ref "MCP6") (pin "9") (pinfunction "SDA_9") (pintype "passive"))
      (node (ref "R37") (pin "2") (pintype "passive"))
      (node (ref "U2") (pin "23") (pinfunction "PC4_(ADC4/SDA/PCINT12)_23") (pintype "bidirectional"))
    )
    (net (code "131") (name "/~{RESET}") (class "Default")
      (node (ref "P10") (pin "10") (pinfunction "10_10") (pintype "passive"))
      (node (ref "P9") (pin "10") (pinfunction "10_10") (pintype "passive"))
      (node (ref "R35") (pin "2") (pintype "passive"))
      (node (ref "U2") (pin "25") (pinfunction "PC6_(PCINT14/~{RESET})_25") (pintype "bidirectional"))
    )
    (net (code "132") (name "/~{SS}") (class "Default")
      (node (ref "P10") (pin "8") (pinfunction "8_8") (pintype "passive"))
      (node (ref "P9") (pin "8") (pinfunction "8_8") (pintype "passive"))
      (node (ref "R30") (pin "1") (pintype "passive"))
    )
    (net (code "133") (name "AGND") (class "Default")
      (node (ref "P5") (pin "12") (pinfunction "12_12") (pintype "passive"))
      (node (ref "P5") (pin "16") (pinfunction "16_16") (pintype "passive"))
      (node (ref "P5") (pin "20") (pinfunction "20_20") (pintype "passive"))
      (node (ref "P5") (pin "4") (pinfunction "4_4") (pintype "passive"))
      (node (ref "P5") (pin "8") (pinfunction "8_8") (pintype "passive"))
      (node (ref "P6") (pin "12") (pinfunction "12_12") (pintype "passive"))
      (node (ref "P6") (pin "16") (pinfunction "16_16") (pintype "passive"))
      (node (ref "P6") (pin "20") (pinfunction "20_20") (pintype "passive"))
      (node (ref "P6") (pin "4") (pinfunction "4_4") (pintype "passive"))
      (node (ref "P6") (pin "8") (pinfunction "8_8") (pintype "passive"))
    )
    (net (code "134") (name "AVCC") (class "Default")
      (node (ref "C33") (pin "1") (pinfunction "1_1") (pintype "passive"))
      (node (ref "FB2") (pin "2") (pintype "passive"))
      (node (ref "U2") (pin "16") (pinfunction "AVCC_16") (pintype "power_in"))
    )
    (net (code "135") (name "GND") (class "Default")
      (node (ref "C10") (pin "1") (pinfunction "1_1") (pintype "passive"))
      (node (ref "C11") (pin "1") (pinfunction "1_1") (pintype "passive"))
      (node (ref "C12") (pin "2") (pinfunction "2_2") (pintype "passive"))
      (node (ref "C13") (pin "2") (pinfunction "2_2") (pintype "passive"))
      (node (ref "C14") (pin "1") (pinfunction "1_1") (pintype "passive"))
      (node (ref "C15") (pin "1") (pinfunction "1_1") (pintype "passive"))
      (node (ref "C16") (pin "2") (pinfunction "2_2") (pintype "passive"))
      (node (ref "C17") (pin "2") (pinfunction "2_2") (pintype "passive"))
      (node (ref "C18") (pin "1") (pinfunction "1_1") (pintype "passive"))
      (node (ref "C19") (pin "1") (pinfunction "1_1") (pintype "passive"))
      (node (ref "C20") (pin "2") (pinfunction "2_2") (pintype "passive"))
      (node (ref "C21") (pin "2") (pinfunction "2_2") (pintype "passive"))
      (node (ref "C22") (pin "1") (pinfunction "1_1") (pintype "passive"))
      (node (ref "C23") (pin "1") (pinfunction "1_1") (pintype "passive"))
      (node (ref "C24") (pin "2") (pinfunction "2_2") (pintype "passive"))
      (node (ref "C25") (pin "2") (pinfunction "2_2") (pintype "passive"))
      (node (ref "C26") (pin "1") (pinfunction "1_1") (pintype "passive"))
      (node (ref "C27") (pin "1") (pinfunction "1_1") (pintype "passive"))
      (node (ref "C28") (pin "2") (pinfunction "2_2") (pintype "passive"))
      (node (ref "C29") (pin "2") (pinfunction "2_2") (pintype "passive"))
      (node (ref "C30") (pin "2") (pinfunction "2_2") (pintype "passive"))
      (node (ref "C31") (pin "2") (pinfunction "2_2") (pintype "passive"))
      (node (ref "C32") (pin "2") (pinfunction "2_2") (pintype "passive"))
      (node (ref "C33") (pin "2") (pinfunction "2_2") (pintype "passive"))
      (node (ref "C34") (pin "2") (pinfunction "2_2") (pintype "passive"))
      (node (ref "C35") (pin "2") (pinfunction "2_2") (pintype "passive"))
      (node (ref "C36") (pin "2") (pinfunction "2_2") (pintype "passive"))
      (node (ref "LD2") (pin "2") (pinfunction "GND_2") (pintype "passive"))
      (node (ref "MCP2") (pin "11") (pinfunction "A0_11") (pintype "passive"))
      (node (ref "MCP2") (pin "12") (pinfunction "A1_12") (pintype "passive"))
      (node (ref "MCP2") (pin "13") (pinfunction "A2_13") (pintype "passive"))
      (node (ref "MCP2") (pin "6") (pinfunction "GND_6") (pintype "passive"))
      (node (ref "MCP3") (pin "12") (pinfunction "A1_12") (pintype "passive"))
      (node (ref "MCP3") (pin "13") (pinfunction "A2_13") (pintype "passive"))
      (node (ref "MCP3") (pin "6") (pinfunction "GND_6") (pintype "passive"))
      (node (ref "MCP4") (pin "11") (pinfunction "A0_11") (pintype "passive"))
      (node (ref "MCP4") (pin "13") (pinfunction "A2_13") (pintype "passive"))
      (node (ref "MCP4") (pin "6") (pinfunction "GND_6") (pintype "passive"))
      (node (ref "MCP5") (pin "13") (pinfunction "A2_13") (pintype "passive"))
      (node (ref "MCP5") (pin "6") (pinfunction "GND_6") (pintype "passive"))
      (node (ref "MCP6") (pin "11") (pinfunction "A0_11") (pintype "passive"))
      (node (ref "MCP6") (pin "12") (pinfunction "A1_12") (pintype "passive"))
      (node (ref "MCP6") (pin "6") (pinfunction "GND_6") (pintype "passive"))
      (node (ref "P10") (pin "1") (pinfunction "1_1") (pintype "passive"))
      (node (ref "P10") (pin "11") (pinfunction "11_11") (pintype "passive"))
      (node (ref "P10") (pin "3") (pinfunction "3_3") (pintype "passive"))
      (node (ref "P10") (pin "5") (pinfunction "5_5") (pintype "passive"))
      (node (ref "P10") (pin "7") (pinfunction "7_7") (pintype "passive"))
      (node (ref "P10") (pin "9") (pinfunction "9_9") (pintype "passive"))
      (node (ref "P7") (pin "1") (pinfunction "1_1") (pintype "passive"))
      (node (ref "P7") (pin "4") (pinfunction "4_4") (pintype "passive"))
      (node (ref "P8") (pin "1") (pinfunction "1_1") (pintype "passive"))
      (node (ref "P8") (pin "4") (pinfunction "4_4") (pintype "passive"))
      (node (ref "P9") (pin "1") (pinfunction "1_1") (pintype "passive"))
      (node (ref "P9") (pin "11") (pinfunction "11_11") (pintype "passive"))
      (node (ref "P9") (pin "3") (pinfunction "3_3") (pintype "passive"))
      (node (ref "P9") (pin "5") (pinfunction "5_5") (pintype "passive"))
      (node (ref "P9") (pin "7") (pinfunction "7_7") (pintype "passive"))
      (node (ref "P9") (pin "9") (pinfunction "9_9") (pintype "passive"))
      (node (ref "U2") (pin "18") (pinfunction "GND_18") (pintype "power_in"))
      (node (ref "U2") (pin "29") (pinfunction "DAP_29") (pintype "passive"))
      (node (ref "U2") (pin "4") (pinfunction "GND_4") (pintype "power_in"))
      (node (ref "ULN10") (pin "21") (pinfunction "PAD_21") (pintype "passive"))
      (node (ref "ULN10") (pin "8") (pinfunction "GND_8") (pintype "passive"))
      (node (ref "ULN11") (pin "21") (pinfunction "PAD_21") (pintype "passive"))
      (node (ref "ULN11") (pin "8") (pinfunction "GND_8") (pintype "passive"))
      (node (ref "ULN12") (pin "21") (pinfunction "PAD_21") (pintype "passive"))
      (node (ref "ULN12") (pin "8") (pinfunction "GND_8") (pintype "passive"))
      (node (ref "ULN3") (pin "21") (pinfunction "PAD_21") (pintype "passive"))
      (node (ref "ULN3") (pin "8") (pinfunction "GND_8") (pintype "passive"))
      (node (ref "ULN4") (pin "21") (pinfunction "PAD_21") (pintype "passive"))
      (node (ref "ULN4") (pin "8") (pinfunction "GND_8") (pintype "passive"))
      (node (ref "ULN5") (pin "21") (pinfunction "PAD_21") (pintype "passive"))
      (node (ref "ULN5") (pin "8") (pinfunction "GND_8") (pintype "passive"))
      (node (ref "ULN6") (pin "21") (pinfunction "PAD_21") (pintype "passive"))
      (node (ref "ULN6") (pin "8") (pinfunction "GND_8") (pintype "passive"))
      (node (ref "ULN7") (pin "21") (pinfunction "PAD_21") (pintype "passive"))
      (node (ref "ULN7") (pin "8") (pinfunction "GND_8") (pintype "passive"))
      (node (ref "ULN8") (pin "21") (pinfunction "PAD_21") (pintype "passive"))
      (node (ref "ULN8") (pin "8") (pinfunction "GND_8") (pintype "passive"))
      (node (ref "ULN9") (pin "21") (pinfunction "PAD_21") (pintype "passive"))
      (node (ref "ULN9") (pin "8") (pinfunction "GND_8") (pintype "passive"))
    )
    (net (code "136") (name "Net-(MCP2-GPA0)") (class "Default")
      (node (ref "MCP2") (pin "17") (pinfunction "GPA0_17") (pintype "passive"))
      (node (ref "ULN3") (pin "6") (pinfunction "B8_6") (pintype "passive"))
    )
    (net (code "137") (name "Net-(MCP2-GPA1)") (class "Default")
      (node (ref "MCP2") (pin "18") (pinfunction "GPA1_18") (pintype "passive"))
      (node (ref "ULN3") (pin "5") (pinfunction "B7_5") (pintype "passive"))
    )
    (net (code "138") (name "Net-(MCP2-GPA2)") (class "Default")
      (node (ref "MCP2") (pin "19") (pinfunction "GPA2_19") (pintype "passive"))
      (node (ref "ULN3") (pin "4") (pinfunction "B6_4") (pintype "passive"))
    )
    (net (code "139") (name "Net-(MCP2-GPA3)") (class "Default")
      (node (ref "MCP2") (pin "20") (pinfunction "GPA3_20") (pintype "passive"))
      (node (ref "ULN3") (pin "3") (pinfunction "B5_3") (pintype "passive"))
    )
    (net (code "140") (name "Net-(MCP2-GPA4)") (class "Default")
      (node (ref "MCP2") (pin "21") (pinfunction "GPA4_21") (pintype "passive"))
      (node (ref "ULN3") (pin "2") (pinfunction "B4_2") (pintype "passive"))
    )
    (net (code "141") (name "Net-(MCP2-GPA5)") (class "Default")
      (node (ref "MCP2") (pin "22") (pinfunction "GPA5_22") (pintype "passive"))
      (node (ref "ULN3") (pin "1") (pinfunction "B3_1") (pintype "passive"))
    )
    (net (code "142") (name "Net-(MCP2-GPA6)") (class "Default")
      (node (ref "MCP2") (pin "23") (pinfunction "GPA6_23") (pintype "passive"))
      (node (ref "ULN3") (pin "20") (pinfunction "B2_20") (pintype "passive"))
    )
    (net (code "143") (name "Net-(MCP2-GPA7)") (class "Default")
      (node (ref "MCP2") (pin "24") (pinfunction "GPA7_24") (pintype "passive"))
      (node (ref "ULN3") (pin "19") (pinfunction "B1_19") (pintype "passive"))
    )
    (net (code "144") (name "Net-(MCP2-GPB0)") (class "Default")
      (node (ref "MCP2") (pin "25") (pinfunction "GPB0_25") (pintype "passive"))
      (node (ref "ULN4") (pin "6") (pinfunction "B8_6") (pintype "passive"))
    )
    (net (code "145") (name "Net-(MCP2-GPB1)") (class "Default")
      (node (ref "MCP2") (pin "26") (pinfunction "GPB1_26") (pintype "passive"))
      (node (ref "ULN4") (pin "5") (pinfunction "B7_5") (pintype "passive"))
    )
    (net (code "146") (name "Net-(MCP2-GPB2)") (class "Default")
      (node (ref "MCP2") (pin "27") (pinfunction "GPB2_27") (pintype "passive"))
      (node (ref "ULN4") (pin "4") (pinfunction "B6_4") (pintype "passive"))
    )
    (net (code "147") (name "Net-(MCP2-GPB3)") (class "Default")
      (node (ref "MCP2") (pin "28") (pinfunction "GPB3_28") (pintype "passive"))
      (node (ref "ULN4") (pin "3") (pinfunction "B5_3") (pintype "passive"))
    )
    (net (code "148") (name "Net-(MCP2-GPB4)") (class "Default")
      (node (ref "MCP2") (pin "1") (pinfunction "GPB4_1") (pintype "passive"))
      (node (ref "ULN4") (pin "2") (pinfunction "B4_2") (pintype "passive"))
    )
    (net (code "149") (name "Net-(MCP2-GPB5)") (class "Default")
      (node (ref "MCP2") (pin "2") (pinfunction "GPB5_2") (pintype "passive"))
      (node (ref "ULN4") (pin "1") (pinfunction "B3_1") (pintype "passive"))
    )
    (net (code "150") (name "Net-(MCP2-GPB6)") (class "Default")
      (node (ref "MCP2") (pin "3") (pinfunction "GPB6_3") (pintype "passive"))
      (node (ref "ULN4") (pin "20") (pinfunction "B2_20") (pintype "passive"))
    )
    (net (code "151") (name "Net-(MCP2-GPB7)") (class "Default")
      (node (ref "MCP2") (pin "4") (pinfunction "GPB7_4") (pintype "passive"))
      (node (ref "ULN4") (pin "19") (pinfunction "B1_19") (pintype "passive"))
    )
    (net (code "152") (name "Net-(MCP2-~{RESET})") (class "Default")
      (node (ref "C11") (pin "2") (pinfunction "2_2") (pintype "passive"))
      (node (ref "MCP2") (pin "14") (pinfunction "~{RESET}_14") (pintype "passive"))
      (node (ref "R26") (pin "2") (pintype "passive"))
    )
    (net (code "153") (name "Net-(MCP3-GPA0)") (class "Default")
      (node (ref "MCP3") (pin "17") (pinfunction "GPA0_17") (pintype "passive"))
      (node (ref "ULN5") (pin "6") (pinfunction "B8_6") (pintype "passive"))
    )
    (net (code "154") (name "Net-(MCP3-GPA1)") (class "Default")
      (node (ref "MCP3") (pin "18") (pinfunction "GPA1_18") (pintype "passive"))
      (node (ref "ULN5") (pin "5") (pinfunction "B7_5") (pintype "passive"))
    )
    (net (code "155") (name "Net-(MCP3-GPA2)") (class "Default")
      (node (ref "MCP3") (pin "19") (pinfunction "GPA2_19") (pintype "passive"))
      (node (ref "ULN5") (pin "4") (pinfunction "B6_4") (pintype "passive"))
    )
    (net (code "156") (name "Net-(MCP3-GPA3)") (class "Default")
      (node (ref "MCP3") (pin "20") (pinfunction "GPA3_20") (pintype "passive"))
      (node (ref "ULN5") (pin "3") (pinfunction "B5_3") (pintype "passive"))
    )
    (net (code "157") (name "Net-(MCP3-GPA4)") (class "Default")
      (node (ref "MCP3") (pin "21") (pinfunction "GPA4_21") (pintype "passive"))
      (node (ref "ULN5") (pin "2") (pinfunction "B4_2") (pintype "passive"))
    )
    (net (code "158") (name "Net-(MCP3-GPA5)") (class "Default")
      (node (ref "MCP3") (pin "22") (pinfunction "GPA5_22") (pintype "passive"))
      (node (ref "ULN5") (pin "1") (pinfunction "B3_1") (pintype "passive"))
    )
    (net (code "159") (name "Net-(MCP3-GPA6)") (class "Default")
      (node (ref "MCP3") (pin "23") (pinfunction "GPA6_23") (pintype "passive"))
      (node (ref "ULN5") (pin "20") (pinfunction "B2_20") (pintype "passive"))
    )
    (net (code "160") (name "Net-(MCP3-GPA7)") (class "Default")
      (node (ref "MCP3") (pin "24") (pinfunction "GPA7_24") (pintype "passive"))
      (node (ref "ULN5") (pin "19") (pinfunction "B1_19") (pintype "passive"))
    )
    (net (code "161") (name "Net-(MCP3-GPB0)") (class "Default")
      (node (ref "MCP3") (pin "25") (pinfunction "GPB0_25") (pintype "passive"))
      (node (ref "ULN6") (pin "6") (pinfunction "B8_6") (pintype "passive"))
    )
    (net (code "162") (name "Net-(MCP3-GPB1)") (class "Default")
      (node (ref "MCP3") (pin "26") (pinfunction "GPB1_26") (pintype "passive"))
      (node (ref "ULN6") (pin "5") (pinfunction "B7_5") (pintype "passive"))
    )
    (net (code "163") (name "Net-(MCP3-GPB2)") (class "Default")
      (node (ref "MCP3") (pin "27") (pinfunction "GPB2_27") (pintype "passive"))
      (node (ref "ULN6") (pin "4") (pinfunction "B6_4") (pintype "passive"))
    )
    (net (code "164") (name "Net-(MCP3-GPB3)") (class "Default")
      (node (ref "MCP3") (pin "28") (pinfunction "GPB3_28") (pintype "passive"))
      (node (ref "ULN6") (pin "3") (pinfunction "B5_3") (pintype "passive"))
    )
    (net (code "165") (name "Net-(MCP3-GPB4)") (class "Default")
      (node (ref "MCP3") (pin "1") (pinfunction "GPB4_1") (pintype "passive"))
      (node (ref "ULN6") (pin "2") (pinfunction "B4_2") (pintype "passive"))
    )
    (net (code "166") (name "Net-(MCP3-GPB5)") (class "Default")
      (node (ref "MCP3") (pin "2") (pinfunction "GPB5_2") (pintype "passive"))
      (node (ref "ULN6") (pin "1") (pinfunction "B3_1") (pintype "passive"))
    )
    (net (code "167") (name "Net-(MCP3-GPB6)") (class "Default")
      (node (ref "MCP3") (pin "3") (pinfunction "GPB6_3") (pintype "passive"))
      (node (ref "ULN6") (pin "20") (pinfunction "B2_20") (pintype "passive"))
    )
    (net (code "168") (name "Net-(MCP3-GPB7)") (class "Default")
      (node (ref "MCP3") (pin "4") (pinfunction "GPB7_4") (pintype "passive"))
      (node (ref "ULN6") (pin "19") (pinfunction "B1_19") (pintype "passive"))
    )
    (net (code "169") (name "Net-(MCP3-~{RESET})") (class "Default")
      (node (ref "C15") (pin "2") (pinfunction "2_2") (pintype "passive"))
      (node (ref "MCP3") (pin "14") (pinfunction "~{RESET}_14") (pintype "passive"))
      (node (ref "R27") (pin "2") (pintype "passive"))
    )
    (net (code "170") (name "Net-(MCP4-GPA0)") (class "Default")
      (node (ref "MCP4") (pin "17") (pinfunction "GPA0_17") (pintype "passive"))
      (node (ref "ULN8") (pin "6") (pinfunction "B8_6") (pintype "passive"))
    )
    (net (code "171") (name "Net-(MCP4-GPA1)") (class "Default")
      (node (ref "MCP4") (pin "18") (pinfunction "GPA1_18") (pintype "passive"))
      (node (ref "ULN8") (pin "5") (pinfunction "B7_5") (pintype "passive"))
    )
    (net (code "172") (name "Net-(MCP4-GPA2)") (class "Default")
      (node (ref "MCP4") (pin "19") (pinfunction "GPA2_19") (pintype "passive"))
      (node (ref "ULN8") (pin "4") (pinfunction "B6_4") (pintype "passive"))
    )
    (net (code "173") (name "Net-(MCP4-GPA3)") (class "Default")
      (node (ref "MCP4") (pin "20") (pinfunction "GPA3_20") (pintype "passive"))
      (node (ref "ULN8") (pin "3") (pinfunction "B5_3") (pintype "passive"))
    )
    (net (code "174") (name "Net-(MCP4-GPA4)") (class "Default")
      (node (ref "MCP4") (pin "21") (pinfunction "GPA4_21") (pintype "passive"))
      (node (ref "ULN8") (pin "2") (pinfunction "B4_2") (pintype "passive"))
    )
    (net (code "175") (name "Net-(MCP4-GPA5)") (class "Default")
      (node (ref "MCP4") (pin "22") (pinfunction "GPA5_22") (pintype "passive"))
      (node (ref "ULN8") (pin "1") (pinfunction "B3_1") (pintype "passive"))
    )
    (net (code "176") (name "Net-(MCP4-GPA6)") (class "Default")
      (node (ref "MCP4") (pin "23") (pinfunction "GPA6_23") (pintype "passive"))
      (node (ref "ULN8") (pin "20") (pinfunction "B2_20") (pintype "passive"))
    )
    (net (code "177") (name "Net-(MCP4-GPA7)") (class "Default")
      (node (ref "MCP4") (pin "24") (pinfunction "GPA7_24") (pintype "passive"))
      (node (ref "ULN8") (pin "19") (pinfunction "B1_19") (pintype "passive"))
    )
    (net (code "178") (name "Net-(MCP4-GPB0)") (class "Default")
      (node (ref "MCP4") (pin "25") (pinfunction "GPB0_25") (pintype "passive"))
      (node (ref "ULN7") (pin "6") (pinfunction "B8_6") (pintype "passive"))
    )
    (net (code "179") (name "Net-(MCP4-GPB1)") (class "Default")
      (node (ref "MCP4") (pin "26") (pinfunction "GPB1_26") (pintype "passive"))
      (node (ref "ULN7") (pin "5") (pinfunction "B7_5") (pintype "passive"))
    )
    (net (code "180") (name "Net-(MCP4-GPB2)") (class "Default")
      (node (ref "MCP4") (pin "27") (pinfunction "GPB2_27") (pintype "passive"))
      (node (ref "ULN7") (pin "4") (pinfunction "B6_4") (pintype "passive"))
    )
    (net (code "181") (name "Net-(MCP4-GPB3)") (class "Default")
      (node (ref "MCP4") (pin "28") (pinfunction "GPB3_28") (pintype "passive"))
      (node (ref "ULN7") (pin "3") (pinfunction "B5_3") (pintype "passive"))
    )
    (net (code "182") (name "Net-(MCP4-GPB4)") (class "Default")
      (node (ref "MCP4") (pin "1") (pinfunction "GPB4_1") (pintype "passive"))
      (node (ref "ULN7") (pin "2") (pinfunction "B4_2") (pintype "passive"))
    )
    (net (code "183") (name "Net-(MCP4-GPB5)") (class "Default")
      (node (ref "MCP4") (pin "2") (pinfunction "GPB5_2") (pintype "passive"))
      (node (ref "ULN7") (pin "1") (pinfunction "B3_1") (pintype "passive"))
    )
    (net (code "184") (name "Net-(MCP4-GPB6)") (class "Default")
      (node (ref "MCP4") (pin "3") (pinfunction "GPB6_3") (pintype "passive"))
      (node (ref "ULN7") (pin "20") (pinfunction "B2_20") (pintype "passive"))
    )
    (net (code "185") (name "Net-(MCP4-GPB7)") (class "Default")
      (node (ref "MCP4") (pin "4") (pinfunction "GPB7_4") (pintype "passive"))
      (node (ref "ULN7") (pin "19") (pinfunction "B1_19") (pintype "passive"))
    )
    (net (code "186") (name "Net-(MCP4-~{RESET})") (class "Default")
      (node (ref "C19") (pin "2") (pinfunction "2_2") (pintype "passive"))
      (node (ref "MCP4") (pin "14") (pinfunction "~{RESET}_14") (pintype "passive"))
      (node (ref "R28") (pin "2") (pintype "passive"))
    )
    (net (code "187") (name "Net-(MCP5-GPA0)") (class "Default")
      (node (ref "MCP5") (pin "17") (pinfunction "GPA0_17") (pintype "passive"))
      (node (ref "ULN10") (pin "6") (pinfunction "B8_6") (pintype "passive"))
    )
    (net (code "188") (name "Net-(MCP5-GPA1)") (class "Default")
      (node (ref "MCP5") (pin "18") (pinfunction "GPA1_18") (pintype "passive"))
      (node (ref "ULN10") (pin "5") (pinfunction "B7_5") (pintype "passive"))
    )
    (net (code "189") (name "Net-(MCP5-GPA2)") (class "Default")
      (node (ref "MCP5") (pin "19") (pinfunction "GPA2_19") (pintype "passive"))
      (node (ref "ULN10") (pin "4") (pinfunction "B6_4") (pintype "passive"))
    )
    (net (code "190") (name "Net-(MCP5-GPA3)") (class "Default")
      (node (ref "MCP5") (pin "20") (pinfunction "GPA3_20") (pintype "passive"))
      (node (ref "ULN10") (pin "3") (pinfunction "B5_3") (pintype "passive"))
    )
    (net (code "191") (name "Net-(MCP5-GPA4)") (class "Default")
      (node (ref "MCP5") (pin "21") (pinfunction "GPA4_21") (pintype "passive"))
      (node (ref "ULN10") (pin "2") (pinfunction "B4_2") (pintype "passive"))
    )
    (net (code "192") (name "Net-(MCP5-GPA5)") (class "Default")
      (node (ref "MCP5") (pin "22") (pinfunction "GPA5_22") (pintype "passive"))
      (node (ref "ULN10") (pin "1") (pinfunction "B3_1") (pintype "passive"))
    )
    (net (code "193") (name "Net-(MCP5-GPA6)") (class "Default")
      (node (ref "MCP5") (pin "23") (pinfunction "GPA6_23") (pintype "passive"))
      (node (ref "ULN10") (pin "20") (pinfunction "B2_20") (pintype "passive"))
    )
    (net (code "194") (name "Net-(MCP5-GPA7)") (class "Default")
      (node (ref "MCP5") (pin "24") (pinfunction "GPA7_24") (pintype "passive"))
      (node (ref "ULN10") (pin "19") (pinfunction "B1_19") (pintype "passive"))
    )
    (net (code "195") (name "Net-(MCP5-GPB0)") (class "Default")
      (node (ref "MCP5") (pin "25") (pinfunction "GPB0_25") (pintype "passive"))
      (node (ref "ULN9") (pin "6") (pinfunction "B8_6") (pintype "passive"))
    )
    (net (code "196") (name "Net-(MCP5-GPB1)") (class "Default")
      (node (ref "MCP5") (pin "26") (pinfunction "GPB1_26") (pintype "passive"))
      (node (ref "ULN9") (pin "5") (pinfunction "B7_5") (pintype "passive"))
    )
    (net (code "197") (name "Net-(MCP5-GPB2)") (class "Default")
      (node (ref "MCP5") (pin "27") (pinfunction "GPB2_27") (pintype "passive"))
      (node (ref "ULN9") (pin "4") (pinfunction "B6_4") (pintype "passive"))
    )
    (net (code "198") (name "Net-(MCP5-GPB3)") (class "Default")
      (node (ref "MCP5") (pin "28") (pinfunction "GPB3_28") (pintype "passive"))
      (node (ref "ULN9") (pin "3") (pinfunction "B5_3") (pintype "passive"))
    )
    (net (code "199") (name "Net-(MCP5-GPB4)") (class "Default")
      (node (ref "MCP5") (pin "1") (pinfunction "GPB4_1") (pintype "passive"))
      (node (ref "ULN9") (pin "2") (pinfunction "B4_2") (pintype "passive"))
    )
    (net (code "200") (name "Net-(MCP5-GPB5)") (class "Default")
      (node (ref "MCP5") (pin "2") (pinfunction "GPB5_2") (pintype "passive"))
      (node (ref "ULN9") (pin "1") (pinfunction "B3_1") (pintype "passive"))
    )
    (net (code "201") (name "Net-(MCP5-GPB6)") (class "Default")
      (node (ref "MCP5") (pin "3") (pinfunction "GPB6_3") (pintype "passive"))
      (node (ref "ULN9") (pin "20") (pinfunction "B2_20") (pintype "passive"))
    )
    (net (code "202") (name "Net-(MCP5-GPB7)") (class "Default")
      (node (ref "MCP5") (pin "4") (pinfunction "GPB7_4") (pintype "passive"))
      (node (ref "ULN9") (pin "19") (pinfunction "B1_19") (pintype "passive"))
    )
    (net (code "203") (name "Net-(MCP5-~{RESET})") (class "Default")
      (node (ref "C23") (pin "2") (pinfunction "2_2") (pintype "passive"))
      (node (ref "MCP5") (pin "14") (pinfunction "~{RESET}_14") (pintype "passive"))
      (node (ref "R29") (pin "2") (pintype "passive"))
    )
    (net (code "204") (name "Net-(MCP6-GPA0)") (class "Default")
      (node (ref "MCP6") (pin "17") (pinfunction "GPA0_17") (pintype "passive"))
      (node (ref "ULN12") (pin "6") (pinfunction "B8_6") (pintype "passive"))
    )
    (net (code "205") (name "Net-(MCP6-GPA1)") (class "Default")
      (node (ref "MCP6") (pin "18") (pinfunction "GPA1_18") (pintype "passive"))
      (node (ref "ULN12") (pin "5") (pinfunction "B7_5") (pintype "passive"))
    )
    (net (code "206") (name "Net-(MCP6-GPA2)") (class "Default")
      (node (ref "MCP6") (pin "19") (pinfunction "GPA2_19") (pintype "passive"))
      (node (ref "ULN12") (pin "4") (pinfunction "B6_4") (pintype "passive"))
    )
    (net (code "207") (name "Net-(MCP6-GPA3)") (class "Default")
      (node (ref "MCP6") (pin "20") (pinfunction "GPA3_20") (pintype "passive"))
      (node (ref "ULN12") (pin "3") (pinfunction "B5_3") (pintype "passive"))
    )
    (net (code "208") (name "Net-(MCP6-GPA4)") (class "Default")
      (node (ref "MCP6") (pin "21") (pinfunction "GPA4_21") (pintype "passive"))
      (node (ref "ULN12") (pin "2") (pinfunction "B4_2") (pintype "passive"))
    )
    (net (code "209") (name "Net-(MCP6-GPA5)") (class "Default")
      (node (ref "MCP6") (pin "22") (pinfunction "GPA5_22") (pintype "passive"))
      (node (ref "ULN12") (pin "1") (pinfunction "B3_1") (pintype "passive"))
    )
    (net (code "210") (name "Net-(MCP6-GPA6)") (class "Default")
      (node (ref "MCP6") (pin "23") (pinfunction "GPA6_23") (pintype "passive"))
      (node (ref "ULN12") (pin "20") (pinfunction "B2_20") (pintype "passive"))
    )
    (net (code "211") (name "Net-(MCP6-GPA7)") (class "Default")
      (node (ref "MCP6") (pin "24") (pinfunction "GPA7_24") (pintype "passive"))
      (node (ref "ULN12") (pin "19") (pinfunction "B1_19") (pintype "passive"))
    )
    (net (code "212") (name "Net-(MCP6-GPB0)") (class "Default")
      (node (ref "MCP6") (pin "25") (pinfunction "GPB0_25") (pintype "passive"))
      (node (ref "ULN11") (pin "6") (pinfunction "B8_6") (pintype "passive"))
    )
    (net (code "213") (name "Net-(MCP6-GPB1)") (class "Default")
      (node (ref "MCP6") (pin "26") (pinfunction "GPB1_26") (pintype "passive"))
      (node (ref "ULN11") (pin "5") (pinfunction "B7_5") (pintype "passive"))
    )
    (net (code "214") (name "Net-(MCP6-GPB2)") (class "Default")
      (node (ref "MCP6") (pin "27") (pinfunction "GPB2_27") (pintype "passive"))
      (node (ref "ULN11") (pin "4") (pinfunction "B6_4") (pintype "passive"))
    )
    (net (code "215") (name "Net-(MCP6-GPB3)") (class "Default")
      (node (ref "MCP6") (pin "28") (pinfunction "GPB3_28") (pintype "passive"))
      (node (ref "ULN11") (pin "3") (pinfunction "B5_3") (pintype "passive"))
    )
    (net (code "216") (name "Net-(MCP6-GPB4)") (class "Default")
      (node (ref "MCP6") (pin "1") (pinfunction "GPB4_1") (pintype "passive"))
      (node (ref "ULN11") (pin "2") (pinfunction "B4_2") (pintype "passive"))
    )
    (net (code "217") (name "Net-(MCP6-GPB5)") (class "Default")
      (node (ref "MCP6") (pin "2") (pinfunction "GPB5_2") (pintype "passive"))
      (node (ref "ULN11") (pin "1") (pinfunction "B3_1") (pintype "passive"))
    )
    (net (code "218") (name "Net-(MCP6-GPB6)") (class "Default")
      (node (ref "MCP6") (pin "3") (pinfunction "GPB6_3") (pintype "passive"))
      (node (ref "ULN11") (pin "20") (pinfunction "B2_20") (pintype "passive"))
    )
    (net (code "219") (name "Net-(MCP6-GPB7)") (class "Default")
      (node (ref "MCP6") (pin "4") (pinfunction "GPB7_4") (pintype "passive"))
      (node (ref "ULN11") (pin "19") (pinfunction "B1_19") (pintype "passive"))
    )
    (net (code "220") (name "Net-(MCP6-~{RESET})") (class "Default")
      (node (ref "C27") (pin "2") (pinfunction "2_2") (pintype "passive"))
      (node (ref "MCP6") (pin "14") (pinfunction "~{RESET}_14") (pintype "passive"))
      (node (ref "R34") (pin "2") (pintype "passive"))
    )
    (net (code "221") (name "Net-(U2-PB2_(~{SS}{slash}OC1B{slash}PCINT2))") (class "Default")
      (node (ref "R30") (pin "2") (pintype "passive"))
      (node (ref "U2") (pin "12") (pinfunction "PB2_(~{SS}/OC1B/PCINT2)_12") (pintype "bidirectional"))
    )
    (net (code "222") (name "Net-(U2-PB3_(MOSI{slash}PCINT3))") (class "Default")
      (node (ref "R31") (pin "2") (pintype "passive"))
      (node (ref "U2") (pin "13") (pinfunction "PB3_(MOSI/PCINT3)_13") (pintype "bidirectional"))
    )
    (net (code "223") (name "Net-(U2-PB5_(SCK{slash}PCINT5))") (class "Default")
      (node (ref "R32") (pin "2") (pintype "passive"))
      (node (ref "U2") (pin "15") (pinfunction "PB5_(SCK/PCINT5)_15") (pintype "bidirectional"))
    )
    (net (code "224") (name "Net-(U2-PB7_(PCINT7))") (class "Default")
      (node (ref "R33") (pin "2") (pintype "passive"))
      (node (ref "U2") (pin "6") (pinfunction "PB7_(PCINT7)_6") (pintype "bidirectional"))
    )
    (net (code "225") (name "unconnected-(LD2-N{slash}C-Pad4)") (class "Default")
      (node (ref "LD2") (pin "4") (pinfunction "N/C_4") (pintype "passive+no_connect"))
    )
    (net (code "226") (name "unconnected-(MCP2-INTA-Pad16)") (class "Default")
      (node (ref "MCP2") (pin "16") (pinfunction "INTA_16") (pintype "passive+no_connect"))
    )
    (net (code "227") (name "unconnected-(MCP2-INTB-Pad15)") (class "Default")
      (node (ref "MCP2") (pin "15") (pinfunction "INTB_15") (pintype "passive+no_connect"))
    )
    (net (code "228") (name "unconnected-(MCP3-INTA-Pad16)") (class "Default")
      (node (ref "MCP3") (pin "16") (pinfunction "INTA_16") (pintype "passive+no_connect"))
    )
    (net (code "229") (name "unconnected-(MCP3-INTB-Pad15)") (class "Default")
      (node (ref "MCP3") (pin "15") (pinfunction "INTB_15") (pintype "passive+no_connect"))
    )
    (net (code "230") (name "unconnected-(MCP4-INTA-Pad16)") (class "Default")
      (node (ref "MCP4") (pin "16") (pinfunction "INTA_16") (pintype "passive+no_connect"))
    )
    (net (code "231") (name "unconnected-(MCP4-INTB-Pad15)") (class "Default")
      (node (ref "MCP4") (pin "15") (pinfunction "INTB_15") (pintype "passive+no_connect"))
    )
    (net (code "232") (name "unconnected-(MCP5-INTA-Pad16)") (class "Default")
      (node (ref "MCP5") (pin "16") (pinfunction "INTA_16") (pintype "passive+no_connect"))
    )
    (net (code "233") (name "unconnected-(MCP5-INTB-Pad15)") (class "Default")
      (node (ref "MCP5") (pin "15") (pinfunction "INTB_15") (pintype "passive+no_connect"))
    )
    (net (code "234") (name "unconnected-(MCP6-INTA-Pad16)") (class "Default")
      (node (ref "MCP6") (pin "16") (pinfunction "INTA_16") (pintype "passive+no_connect"))
    )
    (net (code "235") (name "unconnected-(MCP6-INTB-Pad15)") (class "Default")
      (node (ref "MCP6") (pin "15") (pinfunction "INTB_15") (pintype "passive+no_connect"))
    )
    (net (code "236") (name "unconnected-(U2-PB0_(PCINT0{slash}CLKO{slash}ICP1)-Pad10)") (class "Default")
      (node (ref "U2") (pin "10") (pinfunction "PB0_(PCINT0/CLKO/ICP1)_10") (pintype "bidirectional"))
    )
    (net (code "237") (name "unconnected-(U2-PB1_(OC1A{slash}PCINT1)-Pad11)") (class "Default")
      (node (ref "U2") (pin "11") (pinfunction "PB1_(OC1A/PCINT1)_11") (pintype "bidirectional"))
    )
    (net (code "238") (name "unconnected-(U2-PB6_(PCINT6{slash}CLKI)-Pad5)") (class "Default")
      (node (ref "U2") (pin "5") (pinfunction "PB6_(PCINT6/CLKI)_5") (pintype "bidirectional"))
    )
    (net (code "239") (name "unconnected-(U2-PC0_(ADC0{slash}PCINT8)-Pad19)") (class "Default")
      (node (ref "U2") (pin "19") (pinfunction "PC0_(ADC0/PCINT8)_19") (pintype "bidirectional"))
    )
    (net (code "240") (name "unconnected-(U2-PC1_(ADC1{slash}PCINT9)-Pad20)") (class "Default")
      (node (ref "U2") (pin "20") (pinfunction "PC1_(ADC1/PCINT9)_20") (pintype "bidirectional"))
    )
    (net (code "241") (name "unconnected-(U2-PC2_(ADC2{slash}PCINT10)-Pad21)") (class "Default")
      (node (ref "U2") (pin "21") (pinfunction "PC2_(ADC2/PCINT10)_21") (pintype "bidirectional"))
    )
    (net (code "242") (name "unconnected-(U2-PC3_(ADC3{slash}PCINT11)-Pad22)") (class "Default")
      (node (ref "U2") (pin "22") (pinfunction "PC3_(ADC3/PCINT11)_22") (pintype "bidirectional"))
    )
    (net (code "243") (name "unconnected-(U2-PC7_(PCINT15)-Pad17)") (class "Default")
      (node (ref "U2") (pin "17") (pinfunction "PC7_(PCINT15)_17") (pintype "bidirectional"))
    )
    (net (code "244") (name "unconnected-(U2-PD0_(PCINT16)-Pad26)") (class "Default")
      (node (ref "U2") (pin "26") (pinfunction "PD0_(PCINT16)_26") (pintype "bidirectional"))
    )
    (net (code "245") (name "unconnected-(U2-PD1_(PCINT17)-Pad27)") (class "Default")
      (node (ref "U2") (pin "27") (pinfunction "PD1_(PCINT17)_27") (pintype "bidirectional"))
    )
    (net (code "246") (name "unconnected-(U2-PD2_(PCINT18{slash}INT0)-Pad28)") (class "Default")
      (node (ref "U2") (pin "28") (pinfunction "PD2_(PCINT18/INT0)_28") (pintype "bidirectional"))
    )
    (net (code "247") (name "unconnected-(U2-PD3_(PCINT19{slash}INT1)-Pad1)") (class "Default")
      (node (ref "U2") (pin "1") (pinfunction "PD3_(PCINT19/INT1)_1") (pintype "bidirectional"))
    )
    (net (code "248") (name "unconnected-(U2-PD4_(PCINT20{slash}T0)-Pad2)") (class "Default")
      (node (ref "U2") (pin "2") (pinfunction "PD4_(PCINT20/T0)_2") (pintype "bidirectional"))
    )
    (net (code "249") (name "unconnected-(U2-PD5_(PCINT21{slash}T1)-Pad7)") (class "Default")
      (node (ref "U2") (pin "7") (pinfunction "PD5_(PCINT21/T1)_7") (pintype "bidirectional"))
    )
    (net (code "250") (name "unconnected-(U2-PD6_(PCINT22{slash}AIN0)-Pad8)") (class "Default")
      (node (ref "U2") (pin "8") (pinfunction "PD6_(PCINT22/AIN0)_8") (pintype "bidirectional"))
    )
    (net (code "251") (name "unconnected-(U2-PD7_(PCINT23{slash}AIN1)-Pad9)") (class "Default")
      (node (ref "U2") (pin "9") (pinfunction "PD7_(PCINT23/AIN1)_9") (pintype "bidirectional"))
    )
  )
)
